# SignalProcess.net
KiCad netlist of a schematic drawn in Altium Designer
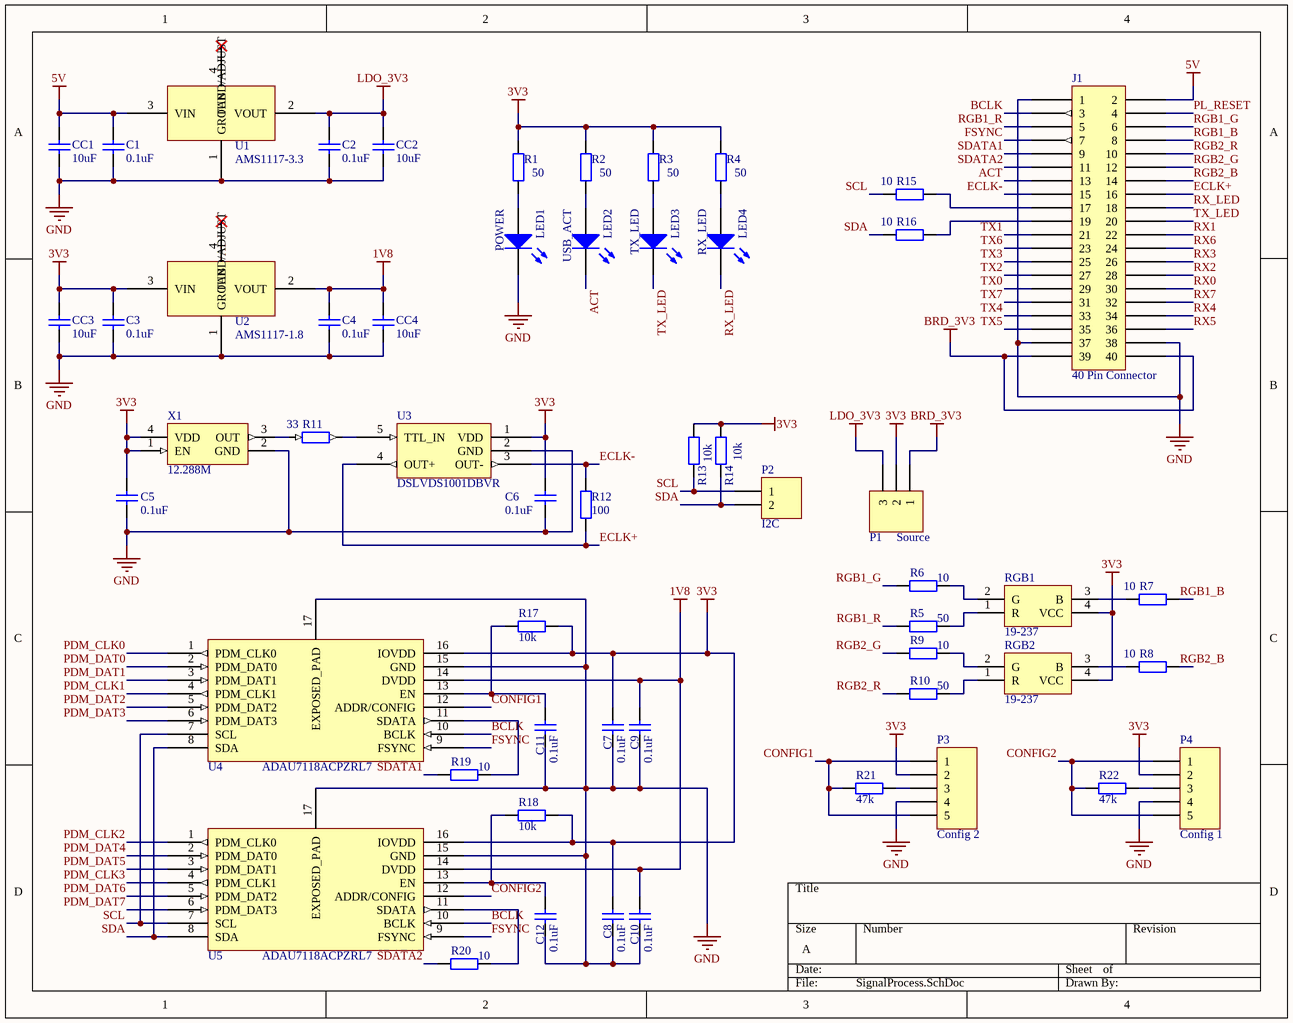
[diagram p0: SignalProcess.SchDoc]

(export (version "E")
  (design (tool "Eeschema 10.0.6"))
  (components
    (comp (ref "C1")
      (value "0.1uF")
      (footprint "CHIP-0603")
      (description "Capacitor")
      (fields (field (name "PUBLISHER") "Altium Limited"))
      (libsource (lib "Miscellaneous Devices") (part "Cap"))
    )
    (comp (ref "C2")
      (value "0.1uF")
      (footprint "CHIP-0603")
      (description "Capacitor")
      (fields (field (name "PUBLISHER") "Altium Limited"))
      (libsource (lib "Miscellaneous Devices") (part "Cap"))
    )
    (comp (ref "C3")
      (value "0.1uF")
      (footprint "CHIP-0603")
      (description "Capacitor")
      (fields (field (name "PUBLISHER") "Altium Limited"))
      (libsource (lib "Miscellaneous Devices") (part "Cap"))
    )
    (comp (ref "C4")
      (value "0.1uF")
      (footprint "CHIP-0603")
      (description "Capacitor")
      (fields (field (name "PUBLISHER") "Altium Limited"))
      (libsource (lib "Miscellaneous Devices") (part "Cap"))
    )
    (comp (ref "C5")
      (value "0.1uF")
      (footprint "CHIP-0603")
      (description "Capacitor")
      (fields (field (name "PUBLISHER") "Altium Limited"))
      (libsource (lib "Miscellaneous Devices") (part "Cap"))
    )
    (comp (ref "C6")
      (value "0.1uF")
      (footprint "CHIP-0603")
      (description "Capacitor")
      (fields (field (name "PUBLISHER") "Altium Limited"))
      (libsource (lib "Miscellaneous Devices") (part "Cap"))
    )
    (comp (ref "C7")
      (value "0.1uF")
      (footprint "CHIP-0603")
      (description "Capacitor")
      (fields (field (name "PUBLISHER") "Altium Limited"))
      (libsource (lib "Miscellaneous Devices") (part "Cap"))
    )
    (comp (ref "C8")
      (value "0.1uF")
      (footprint "CHIP-0603")
      (description "Capacitor")
      (fields (field (name "PUBLISHER") "Altium Limited"))
      (libsource (lib "Miscellaneous Devices") (part "Cap"))
    )
    (comp (ref "C9")
      (value "0.1uF")
      (footprint "CHIP-0603")
      (description "Capacitor")
      (fields (field (name "PUBLISHER") "Altium Limited"))
      (libsource (lib "Miscellaneous Devices") (part "Cap"))
    )
    (comp (ref "C10")
      (value "0.1uF")
      (footprint "CHIP-0603")
      (description "Capacitor")
      (fields (field (name "PUBLISHER") "Altium Limited"))
      (libsource (lib "Miscellaneous Devices") (part "Cap"))
    )
    (comp (ref "C11")
      (value "0.1uF")
      (footprint "CHIP-0603")
      (description "Capacitor")
      (fields (field (name "PUBLISHER") "Altium Limited"))
      (libsource (lib "Miscellaneous Devices") (part "Cap"))
    )
    (comp (ref "C12")
      (value "0.1uF")
      (footprint "CHIP-0603")
      (description "Capacitor")
      (fields (field (name "PUBLISHER") "Altium Limited"))
      (libsource (lib "Miscellaneous Devices") (part "Cap"))
    )
    (comp (ref "CC1")
      (value "10uF")
      (footprint "CHIP-0603")
      (description "Capacitor")
      (fields (field (name "PUBLISHER") "Altium Limited"))
      (libsource (lib "Miscellaneous Devices") (part "Cap"))
    )
    (comp (ref "CC2")
      (value "10uF")
      (footprint "CHIP-0603")
      (description "Capacitor")
      (fields (field (name "PUBLISHER") "Altium Limited"))
      (libsource (lib "Miscellaneous Devices") (part "Cap"))
    )
    (comp (ref "CC3")
      (value "10uF")
      (footprint "CHIP-0603")
      (description "Capacitor")
      (fields (field (name "PUBLISHER") "Altium Limited"))
      (libsource (lib "Miscellaneous Devices") (part "Cap"))
    )
    (comp (ref "CC4")
      (value "10uF")
      (footprint "CHIP-0603")
      (description "Capacitor")
      (fields (field (name "PUBLISHER") "Altium Limited"))
      (libsource (lib "Miscellaneous Devices") (part "Cap"))
    )
    (comp (ref "J1")
      (value "40 Pin Connector")
      (footprint "2x20FemaleHeader")
      (libsource (lib "2x20FemaleHeader") (part "2x20FemaleHeader"))
    )
    (comp (ref "LED1")
      (value "POWER")
      (footprint "CHIP-0805-LED")
      (description "Typical INFRARED GaAs LED")
      (fields (field (name "PUBLISHER") "Altium Limited"))
      (libsource (lib "Miscellaneous Devices") (part "LED0"))
    )
    (comp (ref "LED2")
      (value "USB_ACT")
      (footprint "CHIP-0805-LED")
      (description "Typical INFRARED GaAs LED")
      (fields (field (name "PUBLISHER") "Altium Limited"))
      (libsource (lib "Miscellaneous Devices") (part "LED0"))
    )
    (comp (ref "LED3")
      (value "TX_LED")
      (footprint "CHIP-0805-LED")
      (description "Typical INFRARED GaAs LED")
      (fields (field (name "PUBLISHER") "Altium Limited"))
      (libsource (lib "Miscellaneous Devices") (part "LED0"))
    )
    (comp (ref "LED4")
      (value "RX_LED")
      (footprint "CHIP-0805-LED")
      (description "Typical INFRARED GaAs LED")
      (fields (field (name "PUBLISHER") "Altium Limited"))
      (libsource (lib "Miscellaneous Devices") (part "LED0"))
    )
    (comp (ref "P1")
      (value "Source")
      (footprint "HDR1X3")
      (description "Header, 3-Pin")
      (fields (field (name "PUBLISHER") "Altium Limited"))
      (libsource (lib "Miscellaneous Connectors") (part "Header 3"))
    )
    (comp (ref "P2")
      (value "I2C")
      (footprint "HDR1X2")
      (description "Header, 2-Pin")
      (fields (field (name "PUBLISHER") "Altium Limited"))
      (libsource (lib "Miscellaneous Connectors") (part "Header 2"))
    )
    (comp (ref "P3")
      (value "Config 2")
      (footprint "HDR1X5")
      (description "Header, 5-Pin")
      (fields (field (name "PUBLISHER") "Altium Limited"))
      (libsource (lib "Miscellaneous Connectors") (part "Header 5"))
    )
    (comp (ref "P4")
      (value "Config 1")
      (footprint "HDR1X5")
      (description "Header, 5-Pin")
      (fields (field (name "PUBLISHER") "Altium Limited"))
      (libsource (lib "Miscellaneous Connectors") (part "Header 5"))
    )
    (comp (ref "R1")
      (value "50")
      (footprint "CHIP-0603")
      (description "Resistor")
      (fields (field (name "PUBLISHER") "Altium Limited"))
      (libsource (lib "") (part "Res2_2"))
    )
    (comp (ref "R2")
      (value "50")
      (footprint "CHIP-0603")
      (description "Resistor")
      (fields (field (name "PUBLISHER") "Altium Limited"))
      (libsource (lib "") (part "Res2_2"))
    )
    (comp (ref "R3")
      (value "50")
      (footprint "CHIP-0603")
      (description "Resistor")
      (fields (field (name "PUBLISHER") "Altium Limited"))
      (libsource (lib "") (part "Res2_2"))
    )
    (comp (ref "R4")
      (value "50")
      (footprint "CHIP-0603")
      (description "Resistor")
      (fields (field (name "PUBLISHER") "Altium Limited"))
      (libsource (lib "") (part "Res2_2"))
    )
    (comp (ref "R5")
      (value "50")
      (footprint "CHIP-0603")
      (description "Resistor")
      (fields (field (name "PUBLISHER") "Altium Limited"))
      (libsource (lib "") (part "Res2_1"))
    )
    (comp (ref "R6")
      (value "10")
      (footprint "CHIP-0603")
      (description "Resistor")
      (fields (field (name "PUBLISHER") "Altium Limited"))
      (libsource (lib "Miscellaneous Devices") (part "Res2"))
    )
    (comp (ref "R7")
      (value "10")
      (footprint "CHIP-0603")
      (description "Resistor")
      (fields (field (name "PUBLISHER") "Altium Limited"))
      (libsource (lib "") (part "Res2_1"))
    )
    (comp (ref "R8")
      (value "10")
      (footprint "CHIP-0603")
      (description "Resistor")
      (fields (field (name "PUBLISHER") "Altium Limited"))
      (libsource (lib "") (part "Res2_1"))
    )
    (comp (ref "R9")
      (value "10")
      (footprint "CHIP-0603")
      (description "Resistor")
      (fields (field (name "PUBLISHER") "Altium Limited"))
      (libsource (lib "Miscellaneous Devices") (part "Res2"))
    )
    (comp (ref "R10")
      (value "50")
      (footprint "CHIP-0603")
      (description "Resistor")
      (fields (field (name "PUBLISHER") "Altium Limited"))
      (libsource (lib "") (part "Res2_1"))
    )
    (comp (ref "R11")
      (value "33")
      (footprint "CHIP-0603")
      (description "Resistor")
      (fields (field (name "PUBLISHER") "Altium Limited"))
      (libsource (lib "") (part "Res2_4"))
    )
    (comp (ref "R12")
      (value "100")
      (footprint "CHIP-0603")
      (description "Resistor")
      (fields (field (name "PUBLISHER") "Altium Limited"))
      (libsource (lib "") (part "Res2_3"))
    )
    (comp (ref "R13")
      (value "10k")
      (footprint "CHIP-0603")
      (description "Resistor")
      (fields (field (name "PUBLISHER") "Altium Limited"))
      (libsource (lib "") (part "Res2_2"))
    )
    (comp (ref "R14")
      (value "10k")
      (footprint "CHIP-0603")
      (description "Resistor")
      (fields (field (name "PUBLISHER") "Altium Limited"))
      (libsource (lib "") (part "Res2_2"))
    )
    (comp (ref "R15")
      (value "10")
      (footprint "CHIP-0603")
      (description "Resistor")
      (fields (field (name "PUBLISHER") "Altium Limited"))
      (libsource (lib "") (part "Res2_1"))
    )
    (comp (ref "R16")
      (value "10")
      (footprint "CHIP-0603")
      (description "Resistor")
      (fields (field (name "PUBLISHER") "Altium Limited"))
      (libsource (lib "") (part "Res2_1"))
    )
    (comp (ref "R17")
      (value "10k")
      (footprint "CHIP-0603")
      (description "Resistor")
      (fields (field (name "PUBLISHER") "Altium Limited"))
      (libsource (lib "") (part "Res2_1"))
    )
    (comp (ref "R18")
      (value "10k")
      (footprint "CHIP-0603")
      (description "Resistor")
      (fields (field (name "PUBLISHER") "Altium Limited"))
      (libsource (lib "") (part "Res2_1"))
    )
    (comp (ref "R19")
      (value "10")
      (footprint "CHIP-0603")
      (description "Resistor")
      (fields (field (name "PUBLISHER") "Altium Limited"))
      (libsource (lib "") (part "Res2_1"))
    )
    (comp (ref "R20")
      (value "10")
      (footprint "CHIP-0603")
      (description "Resistor")
      (fields (field (name "PUBLISHER") "Altium Limited"))
      (libsource (lib "") (part "Res2_1"))
    )
    (comp (ref "R21")
      (value "47k")
      (footprint "CHIP-0603")
      (description "Resistor")
      (fields (field (name "PUBLISHER") "Altium Limited"))
      (libsource (lib "") (part "Res2_1"))
    )
    (comp (ref "R22")
      (value "47k")
      (footprint "CHIP-0603")
      (description "Resistor")
      (fields (field (name "PUBLISHER") "Altium Limited"))
      (libsource (lib "") (part "Res2_1"))
    )
    (comp (ref "RGB1")
      (value "19-237")
      (footprint "19-237-R6GHBHC")
      (libsource (lib "19-237-R6GHBHC") (part "19-237-R6GHBHC"))
    )
    (comp (ref "RGB2")
      (value "19-237")
      (footprint "19-237-R6GHBHC")
      (libsource (lib "19-237-R6GHBHC") (part "19-237-R6GHBHC"))
    )
    (comp (ref "U1")
      (value "AMS1117-3.3")
      (footprint "SOT223_AMS1117-1.8_AMS")
      (description "No Description Available")
      (fields
        (field (name "MANUFACTURER_PART_NUMBER") "AMS1117-1.8")
        (field (name "COPYRIGHT") "Copyright (C) 2023 Ultra Librarian. All rights reserved.")
      )
      (libsource (lib "AMS1117-1P8") (part "AMS1117-1.8"))
    )
    (comp (ref "U2")
      (value "AMS1117-1.8")
      (footprint "SOT223_AMS1117-1.8_AMS")
      (description "No Description Available")
      (fields (field (name "COPYRIGHT") "Copyright (C) 2023 Ultra Librarian. All rights reserved."))
      (libsource (lib "AMS1117-1P8") (part "AMS1117-1.8"))
    )
    (comp (ref "U3")
      (value "DSLVDS1001DBVR")
      (footprint "SOT-23-5_2P9X1P6_TEX")
      (description "No Description Available")
      (libsource (lib "DSLVDS1001DBVR") (part "DSLVDS1001DBVR"))
    )
    (comp (ref "U4")
      (value "ADAU7118ACPZRL7")
      (footprint "QFN50P300X300X80-17N")
      (libsource (lib "ADAU7118ACPZRL7") (part "ADAU7118ACPZRL7"))
    )
    (comp (ref "U5")
      (value "ADAU7118ACPZRL7")
      (footprint "QFN50P300X300X80-17N")
      (libsource (lib "ADAU7118ACPZRL7") (part "ADAU7118ACPZRL7"))
    )
    (comp (ref "X1")
      (value "12.288M")
      (footprint "S3D12.288000B20F30T")
      (libsource (lib "S3D12.288000B20F30T") (part "S3D12.288000B20F30T"))
    )
  )
  (nets
    (net (code "1") (name "/ACT") (class "Default")
      (node (ref "J1") (pin "13") (pinfunction "13_13") (pintype "passive"))
      (node (ref "LED2") (pin "2") (pinfunction "K_2") (pintype "passive"))
    )
    (net (code "2") (name "/BCLK") (class "Default")
      (node (ref "J1") (pin "3") (pinfunction "3_3") (pintype "output"))
      (node (ref "U4") (pin "10") (pinfunction "BCLK_10") (pintype "input"))
      (node (ref "U5") (pin "10") (pinfunction "BCLK_10") (pintype "input"))
    )
    (net (code "3") (name "/CONFIG1") (class "Default")
      (node (ref "P3") (pin "1") (pinfunction "1_1") (pintype "passive"))
      (node (ref "P3") (pin "5") (pinfunction "5_5") (pintype "passive"))
      (node (ref "R21") (pin "1") (pinfunction "1_1") (pintype "passive"))
      (node (ref "U4") (pin "12") (pinfunction "ADDR/CONFIG_12") (pintype "passive"))
    )
    (net (code "4") (name "/CONFIG2") (class "Default")
      (node (ref "P4") (pin "1") (pinfunction "1_1") (pintype "passive"))
      (node (ref "P4") (pin "5") (pinfunction "5_5") (pintype "passive"))
      (node (ref "R22") (pin "1") (pinfunction "1_1") (pintype "passive"))
      (node (ref "U5") (pin "12") (pinfunction "ADDR/CONFIG_12") (pintype "passive"))
    )
    (net (code "5") (name "/ECLK+") (class "Default")
      (node (ref "J1") (pin "16") (pinfunction "16_16") (pintype "passive"))
      (node (ref "R12") (pin "2") (pinfunction "2_2") (pintype "passive"))
      (node (ref "U3") (pin "4") (pinfunction "OUT+_4") (pintype "output"))
    )
    (net (code "6") (name "/ECLK-") (class "Default")
      (node (ref "J1") (pin "15") (pinfunction "15_15") (pintype "passive"))
      (node (ref "R12") (pin "1") (pinfunction "1_1") (pintype "passive"))
      (node (ref "U3") (pin "3") (pinfunction "OUT-_3") (pintype "output"))
    )
    (net (code "7") (name "/FSYNC") (class "Default")
      (node (ref "J1") (pin "7") (pinfunction "7_7") (pintype "output"))
      (node (ref "U4") (pin "9") (pinfunction "FSYNC_9") (pintype "input"))
      (node (ref "U5") (pin "9") (pinfunction "FSYNC_9") (pintype "input"))
    )
    (net (code "8") (name "/PDM_CLK0") (class "Default")
      (node (ref "U4") (pin "1") (pinfunction "PDM_CLK0_1") (pintype "output"))
    )
    (net (code "9") (name "/PDM_CLK1") (class "Default")
      (node (ref "U4") (pin "4") (pinfunction "PDM_CLK1_4") (pintype "output"))
    )
    (net (code "10") (name "/PDM_CLK2") (class "Default")
      (node (ref "U5") (pin "1") (pinfunction "PDM_CLK0_1") (pintype "output"))
    )
    (net (code "11") (name "/PDM_CLK3") (class "Default")
      (node (ref "U5") (pin "4") (pinfunction "PDM_CLK1_4") (pintype "output"))
    )
    (net (code "12") (name "/PDM_DAT0") (class "Default")
      (node (ref "U4") (pin "2") (pinfunction "PDM_DAT0_2") (pintype "input"))
    )
    (net (code "13") (name "/PDM_DAT1") (class "Default")
      (node (ref "U4") (pin "3") (pinfunction "PDM_DAT1_3") (pintype "input"))
    )
    (net (code "14") (name "/PDM_DAT2") (class "Default")
      (node (ref "U4") (pin "5") (pinfunction "PDM_DAT2_5") (pintype "input"))
    )
    (net (code "15") (name "/PDM_DAT3") (class "Default")
      (node (ref "U4") (pin "6") (pinfunction "PDM_DAT3_6") (pintype "input"))
    )
    (net (code "16") (name "/PDM_DAT4") (class "Default")
      (node (ref "U5") (pin "2") (pinfunction "PDM_DAT0_2") (pintype "input"))
    )
    (net (code "17") (name "/PDM_DAT5") (class "Default")
      (node (ref "U5") (pin "3") (pinfunction "PDM_DAT1_3") (pintype "input"))
    )
    (net (code "18") (name "/PDM_DAT6") (class "Default")
      (node (ref "U5") (pin "5") (pinfunction "PDM_DAT2_5") (pintype "input"))
    )
    (net (code "19") (name "/PDM_DAT7") (class "Default")
      (node (ref "U5") (pin "6") (pinfunction "PDM_DAT3_6") (pintype "input"))
    )
    (net (code "20") (name "/PL_RESET") (class "Default")
      (node (ref "J1") (pin "4") (pinfunction "4_4") (pintype "passive"))
    )
    (net (code "21") (name "/RGB1_B") (class "Default")
      (node (ref "J1") (pin "8") (pinfunction "8_8") (pintype "passive"))
      (node (ref "R7") (pin "2") (pinfunction "2_2") (pintype "passive"))
    )
    (net (code "22") (name "/RGB1_G") (class "Default")
      (node (ref "J1") (pin "6") (pinfunction "6_6") (pintype "passive"))
      (node (ref "R6") (pin "2") (pinfunction "2_2") (pintype "passive"))
    )
    (net (code "23") (name "/RGB1_R") (class "Default")
      (node (ref "J1") (pin "5") (pinfunction "5_5") (pintype "passive"))
      (node (ref "R5") (pin "1") (pinfunction "1_1") (pintype "passive"))
    )
    (net (code "24") (name "/RGB2_B") (class "Default")
      (node (ref "J1") (pin "14") (pinfunction "14_14") (pintype "passive"))
      (node (ref "R8") (pin "2") (pinfunction "2_2") (pintype "passive"))
    )
    (net (code "25") (name "/RGB2_G") (class "Default")
      (node (ref "J1") (pin "12") (pinfunction "12_12") (pintype "passive"))
      (node (ref "R9") (pin "2") (pinfunction "2_2") (pintype "passive"))
    )
    (net (code "26") (name "/RGB2_R") (class "Default")
      (node (ref "J1") (pin "10") (pinfunction "10_10") (pintype "passive"))
      (node (ref "R10") (pin "1") (pinfunction "1_1") (pintype "passive"))
    )
    (net (code "27") (name "/RX0") (class "Default")
      (node (ref "J1") (pin "30") (pinfunction "30_30") (pintype "passive"))
    )
    (net (code "28") (name "/RX1") (class "Default")
      (node (ref "J1") (pin "22") (pinfunction "22_22") (pintype "passive"))
    )
    (net (code "29") (name "/RX2") (class "Default")
      (node (ref "J1") (pin "28") (pinfunction "28_28") (pintype "passive"))
    )
    (net (code "30") (name "/RX3") (class "Default")
      (node (ref "J1") (pin "26") (pinfunction "26_26") (pintype "passive"))
    )
    (net (code "31") (name "/RX4") (class "Default")
      (node (ref "J1") (pin "34") (pinfunction "34_34") (pintype "passive"))
    )
    (net (code "32") (name "/RX5") (class "Default")
      (node (ref "J1") (pin "36") (pinfunction "36_36") (pintype "passive"))
    )
    (net (code "33") (name "/RX6") (class "Default")
      (node (ref "J1") (pin "24") (pinfunction "24_24") (pintype "passive"))
    )
    (net (code "34") (name "/RX7") (class "Default")
      (node (ref "J1") (pin "32") (pinfunction "32_32") (pintype "passive"))
    )
    (net (code "35") (name "/RX_LED") (class "Default")
      (node (ref "J1") (pin "18") (pinfunction "18_18") (pintype "passive"))
      (node (ref "LED4") (pin "2") (pinfunction "K_2") (pintype "passive"))
    )
    (net (code "36") (name "/SCL") (class "Default")
      (node (ref "P2") (pin "1") (pinfunction "1_1") (pintype "passive"))
      (node (ref "R13") (pin "1") (pinfunction "1_1") (pintype "passive"))
      (node (ref "R15") (pin "1") (pinfunction "1_1") (pintype "passive"))
      (node (ref "U4") (pin "7") (pinfunction "SCL_7") (pintype "passive"))
      (node (ref "U5") (pin "7") (pinfunction "SCL_7") (pintype "passive"))
    )
    (net (code "37") (name "/SDA") (class "Default")
      (node (ref "P2") (pin "2") (pinfunction "2_2") (pintype "passive"))
      (node (ref "R14") (pin "1") (pinfunction "1_1") (pintype "passive"))
      (node (ref "R16") (pin "1") (pinfunction "1_1") (pintype "passive"))
      (node (ref "U4") (pin "8") (pinfunction "SDA_8") (pintype "passive"))
      (node (ref "U5") (pin "8") (pinfunction "SDA_8") (pintype "passive"))
    )
    (net (code "38") (name "/SDATA1") (class "Default")
      (node (ref "J1") (pin "9") (pinfunction "9_9") (pintype "passive"))
      (node (ref "R19") (pin "1") (pinfunction "1_1") (pintype "passive"))
    )
    (net (code "39") (name "/SDATA2") (class "Default")
      (node (ref "J1") (pin "11") (pinfunction "11_11") (pintype "passive"))
      (node (ref "R20") (pin "1") (pinfunction "1_1") (pintype "passive"))
    )
    (net (code "40") (name "/TX0") (class "Default")
      (node (ref "J1") (pin "29") (pinfunction "29_29") (pintype "passive"))
    )
    (net (code "41") (name "/TX1") (class "Default")
      (node (ref "J1") (pin "21") (pinfunction "21_21") (pintype "passive"))
    )
    (net (code "42") (name "/TX2") (class "Default")
      (node (ref "J1") (pin "27") (pinfunction "27_27") (pintype "passive"))
    )
    (net (code "43") (name "/TX3") (class "Default")
      (node (ref "J1") (pin "25") (pinfunction "25_25") (pintype "passive"))
    )
    (net (code "44") (name "/TX4") (class "Default")
      (node (ref "J1") (pin "33") (pinfunction "33_33") (pintype "passive"))
    )
    (net (code "45") (name "/TX5") (class "Default")
      (node (ref "J1") (pin "35") (pinfunction "35_35") (pintype "passive"))
    )
    (net (code "46") (name "/TX6") (class "Default")
      (node (ref "J1") (pin "23") (pinfunction "23_23") (pintype "passive"))
    )
    (net (code "47") (name "/TX7") (class "Default")
      (node (ref "J1") (pin "31") (pinfunction "31_31") (pintype "passive"))
    )
    (net (code "48") (name "/TX_LED") (class "Default")
      (node (ref "J1") (pin "20") (pinfunction "20_20") (pintype "passive"))
      (node (ref "LED3") (pin "2") (pinfunction "K_2") (pintype "passive"))
    )
    (net (code "49") (name "1V8") (class "Default")
      (node (ref "C10") (pin "2") (pinfunction "2_2") (pintype "passive"))
      (node (ref "C4") (pin "2") (pinfunction "2_2") (pintype "passive"))
      (node (ref "C9") (pin "2") (pinfunction "2_2") (pintype "passive"))
      (node (ref "CC4") (pin "2") (pinfunction "2_2") (pintype "passive"))
      (node (ref "U2") (pin "2") (pinfunction "VOUT_2") (pintype "passive"))
      (node (ref "U4") (pin "14") (pinfunction "DVDD_14") (pintype "power_in"))
      (node (ref "U5") (pin "14") (pinfunction "DVDD_14") (pintype "power_in"))
    )
    (net (code "50") (name "3V3") (class "Default")
      (node (ref "C3") (pin "2") (pinfunction "2_2") (pintype "passive"))
      (node (ref "C5") (pin "2") (pinfunction "2_2") (pintype "passive"))
      (node (ref "C6") (pin "2") (pinfunction "2_2") (pintype "passive"))
      (node (ref "C7") (pin "2") (pinfunction "2_2") (pintype "passive"))
      (node (ref "C8") (pin "2") (pinfunction "2_2") (pintype "passive"))
      (node (ref "CC3") (pin "2") (pinfunction "2_2") (pintype "passive"))
      (node (ref "P1") (pin "2") (pinfunction "2_2") (pintype "passive"))
      (node (ref "P3") (pin "2") (pinfunction "2_2") (pintype "passive"))
      (node (ref "P4") (pin "2") (pinfunction "2_2") (pintype "passive"))
      (node (ref "R1") (pin "2") (pinfunction "2_2") (pintype "passive"))
      (node (ref "R13") (pin "2") (pinfunction "2_2") (pintype "passive"))
      (node (ref "R14") (pin "2") (pinfunction "2_2") (pintype "passive"))
      (node (ref "R17") (pin "2") (pinfunction "2_2") (pintype "passive"))
      (node (ref "R18") (pin "2") (pinfunction "2_2") (pintype "passive"))
      (node (ref "R2") (pin "2") (pinfunction "2_2") (pintype "passive"))
      (node (ref "R3") (pin "2") (pinfunction "2_2") (pintype "passive"))
      (node (ref "R4") (pin "2") (pinfunction "2_2") (pintype "passive"))
      (node (ref "RGB1") (pin "4") (pinfunction "VCC_4") (pintype "passive"))
      (node (ref "RGB2") (pin "4") (pinfunction "VCC_4") (pintype "passive"))
      (node (ref "U2") (pin "3") (pinfunction "VIN_3") (pintype "passive"))
      (node (ref "U3") (pin "1") (pinfunction "VDD_1") (pintype "power_in"))
      (node (ref "U4") (pin "16") (pinfunction "IOVDD_16") (pintype "power_in"))
      (node (ref "U5") (pin "16") (pinfunction "IOVDD_16") (pintype "power_in"))
      (node (ref "X1") (pin "1") (pinfunction "EN_1") (pintype "input"))
      (node (ref "X1") (pin "4") (pinfunction "VDD_4") (pintype "power_in"))
    )
    (net (code "51") (name "5V") (class "Default")
      (node (ref "C1") (pin "2") (pinfunction "2_2") (pintype "passive"))
      (node (ref "CC1") (pin "2") (pinfunction "2_2") (pintype "passive"))
      (node (ref "J1") (pin "2") (pinfunction "2_2") (pintype "power_in"))
      (node (ref "U1") (pin "3") (pinfunction "VIN_3") (pintype "passive"))
    )
    (net (code "52") (name "BRD_3V3") (class "Default")
      (node (ref "J1") (pin "39") (pinfunction "39_39") (pintype "power_in"))
      (node (ref "J1") (pin "40") (pinfunction "40_40") (pintype "power_in"))
      (node (ref "P1") (pin "1") (pinfunction "1_1") (pintype "passive"))
    )
    (net (code "53") (name "GND") (class "Default")
      (node (ref "C1") (pin "1") (pinfunction "1_1") (pintype "passive"))
      (node (ref "C10") (pin "1") (pinfunction "1_1") (pintype "passive"))
      (node (ref "C11") (pin "1") (pinfunction "1_1") (pintype "passive"))
      (node (ref "C12") (pin "1") (pinfunction "1_1") (pintype "passive"))
      (node (ref "C2") (pin "1") (pinfunction "1_1") (pintype "passive"))
      (node (ref "C3") (pin "1") (pinfunction "1_1") (pintype "passive"))
      (node (ref "C4") (pin "1") (pinfunction "1_1") (pintype "passive"))
      (node (ref "C5") (pin "1") (pinfunction "1_1") (pintype "passive"))
      (node (ref "C6") (pin "1") (pinfunction "1_1") (pintype "passive"))
      (node (ref "C7") (pin "1") (pinfunction "1_1") (pintype "passive"))
      (node (ref "C8") (pin "1") (pinfunction "1_1") (pintype "passive"))
      (node (ref "C9") (pin "1") (pinfunction "1_1") (pintype "passive"))
      (node (ref "CC1") (pin "1") (pinfunction "1_1") (pintype "passive"))
      (node (ref "CC2") (pin "1") (pinfunction "1_1") (pintype "passive"))
      (node (ref "CC3") (pin "1") (pinfunction "1_1") (pintype "passive"))
      (node (ref "CC4") (pin "1") (pinfunction "1_1") (pintype "passive"))
      (node (ref "J1") (pin "1") (pinfunction "1_1") (pintype "power_in"))
      (node (ref "J1") (pin "37") (pinfunction "37_37") (pintype "power_in"))
      (node (ref "J1") (pin "38") (pinfunction "38_38") (pintype "power_in"))
      (node (ref "LED1") (pin "2") (pinfunction "K_2") (pintype "passive"))
      (node (ref "P3") (pin "4") (pinfunction "4_4") (pintype "passive"))
      (node (ref "P4") (pin "4") (pinfunction "4_4") (pintype "passive"))
      (node (ref "U1") (pin "1") (pinfunction "GROUND/ADJUST_1") (pintype "passive"))
      (node (ref "U2") (pin "1") (pinfunction "GROUND/ADJUST_1") (pintype "passive"))
      (node (ref "U3") (pin "2") (pinfunction "GND_2") (pintype "power_in"))
      (node (ref "U4") (pin "15") (pinfunction "GND_15") (pintype "power_in"))
      (node (ref "U4") (pin "17") (pinfunction "EXPOSED_PAD_17") (pintype "power_in"))
      (node (ref "U5") (pin "15") (pinfunction "GND_15") (pintype "power_in"))
      (node (ref "U5") (pin "17") (pinfunction "EXPOSED_PAD_17") (pintype "power_in"))
      (node (ref "X1") (pin "2") (pinfunction "GND_2") (pintype "power_in"))
    )
    (net (code "54") (name "LDO_3V3") (class "Default")
      (node (ref "C2") (pin "2") (pinfunction "2_2") (pintype "passive"))
      (node (ref "CC2") (pin "2") (pinfunction "2_2") (pintype "passive"))
      (node (ref "P1") (pin "3") (pinfunction "3_3") (pintype "passive"))
      (node (ref "U1") (pin "2") (pinfunction "VOUT_2") (pintype "passive"))
    )
    (net (code "55") (name "Net-(J1-Pad17)") (class "Default")
      (node (ref "J1") (pin "17") (pinfunction "17_17") (pintype "passive"))
      (node (ref "R15") (pin "2") (pinfunction "2_2") (pintype "passive"))
    )
    (net (code "56") (name "Net-(J1-Pad19)") (class "Default")
      (node (ref "J1") (pin "19") (pinfunction "19_19") (pintype "passive"))
      (node (ref "R16") (pin "2") (pinfunction "2_2") (pintype "passive"))
    )
    (net (code "57") (name "Net-(LED1-A)") (class "Default")
      (node (ref "LED1") (pin "1") (pinfunction "A_1") (pintype "passive"))
      (node (ref "R1") (pin "1") (pinfunction "1_1") (pintype "passive"))
    )
    (net (code "58") (name "Net-(LED2-A)") (class "Default")
      (node (ref "LED2") (pin "1") (pinfunction "A_1") (pintype "passive"))
      (node (ref "R2") (pin "1") (pinfunction "1_1") (pintype "passive"))
    )
    (net (code "59") (name "Net-(LED3-A)") (class "Default")
      (node (ref "LED3") (pin "1") (pinfunction "A_1") (pintype "passive"))
      (node (ref "R3") (pin "1") (pinfunction "1_1") (pintype "passive"))
    )
    (net (code "60") (name "Net-(LED4-A)") (class "Default")
      (node (ref "LED4") (pin "1") (pinfunction "A_1") (pintype "passive"))
      (node (ref "R4") (pin "1") (pinfunction "1_1") (pintype "passive"))
    )
    (net (code "61") (name "Net-(P3-Pad3)") (class "Default")
      (node (ref "P3") (pin "3") (pinfunction "3_3") (pintype "passive"))
      (node (ref "R21") (pin "2") (pinfunction "2_2") (pintype "passive"))
    )
    (net (code "62") (name "Net-(P4-Pad3)") (class "Default")
      (node (ref "P4") (pin "3") (pinfunction "3_3") (pintype "passive"))
      (node (ref "R22") (pin "2") (pinfunction "2_2") (pintype "passive"))
    )
    (net (code "63") (name "Net-(RGB1-B)") (class "Default")
      (node (ref "R7") (pin "1") (pinfunction "1_1") (pintype "passive"))
      (node (ref "RGB1") (pin "3") (pinfunction "B_3") (pintype "passive"))
    )
    (net (code "64") (name "Net-(RGB1-G)") (class "Default")
      (node (ref "R6") (pin "1") (pinfunction "1_1") (pintype "passive"))
      (node (ref "RGB1") (pin "2") (pinfunction "G_2") (pintype "passive"))
    )
    (net (code "65") (name "Net-(RGB1-R)") (class "Default")
      (node (ref "R5") (pin "2") (pinfunction "2_2") (pintype "passive"))
      (node (ref "RGB1") (pin "1") (pinfunction "R_1") (pintype "passive"))
    )
    (net (code "66") (name "Net-(RGB2-B)") (class "Default")
      (node (ref "R8") (pin "1") (pinfunction "1_1") (pintype "passive"))
      (node (ref "RGB2") (pin "3") (pinfunction "B_3") (pintype "passive"))
    )
    (net (code "67") (name "Net-(RGB2-G)") (class "Default")
      (node (ref "R9") (pin "1") (pinfunction "1_1") (pintype "passive"))
      (node (ref "RGB2") (pin "2") (pinfunction "G_2") (pintype "passive"))
    )
    (net (code "68") (name "Net-(RGB2-R)") (class "Default")
      (node (ref "R10") (pin "2") (pinfunction "2_2") (pintype "passive"))
      (node (ref "RGB2") (pin "1") (pinfunction "R_1") (pintype "passive"))
    )
    (net (code "69") (name "Net-(U3-TTL_IN)") (class "Default")
      (node (ref "R11") (pin "2") (pinfunction "2_2") (pintype "output"))
      (node (ref "U3") (pin "5") (pinfunction "TTL_IN_5") (pintype "input"))
    )
    (net (code "70") (name "Net-(U4-EN)") (class "Default")
      (node (ref "C11") (pin "2") (pinfunction "2_2") (pintype "passive"))
      (node (ref "R17") (pin "1") (pinfunction "1_1") (pintype "passive"))
      (node (ref "U4") (pin "13") (pinfunction "EN_13") (pintype "passive"))
    )
    (net (code "71") (name "Net-(U4-SDATA)") (class "Default")
      (node (ref "R19") (pin "2") (pinfunction "2_2") (pintype "passive"))
      (node (ref "U4") (pin "11") (pinfunction "SDATA_11") (pintype "output"))
    )
    (net (code "72") (name "Net-(U5-EN)") (class "Default")
      (node (ref "C12") (pin "2") (pinfunction "2_2") (pintype "passive"))
      (node (ref "R18") (pin "1") (pinfunction "1_1") (pintype "passive"))
      (node (ref "U5") (pin "13") (pinfunction "EN_13") (pintype "passive"))
    )
    (net (code "73") (name "Net-(U5-SDATA)") (class "Default")
      (node (ref "R20") (pin "2") (pinfunction "2_2") (pintype "passive"))
      (node (ref "U5") (pin "11") (pinfunction "SDATA_11") (pintype "output"))
    )
    (net (code "74") (name "Net-(X1-OUT)") (class "Default")
      (node (ref "R11") (pin "1") (pinfunction "1_1") (pintype "input"))
      (node (ref "X1") (pin "3") (pinfunction "OUT_3") (pintype "output"))
    )
    (net (code "75") (name "unconnected-(U1-TAB-Pad4)") (class "Default")
      (node (ref "U1") (pin "4") (pinfunction "TAB_4") (pintype "passive+no_connect"))
    )
    (net (code "76") (name "unconnected-(U2-TAB-Pad4)") (class "Default")
      (node (ref "U2") (pin "4") (pinfunction "TAB_4") (pintype "passive+no_connect"))
    )
  )
)
